# FCStellarisSCH.net
KiCad netlist of a schematic drawn in Altium Designer
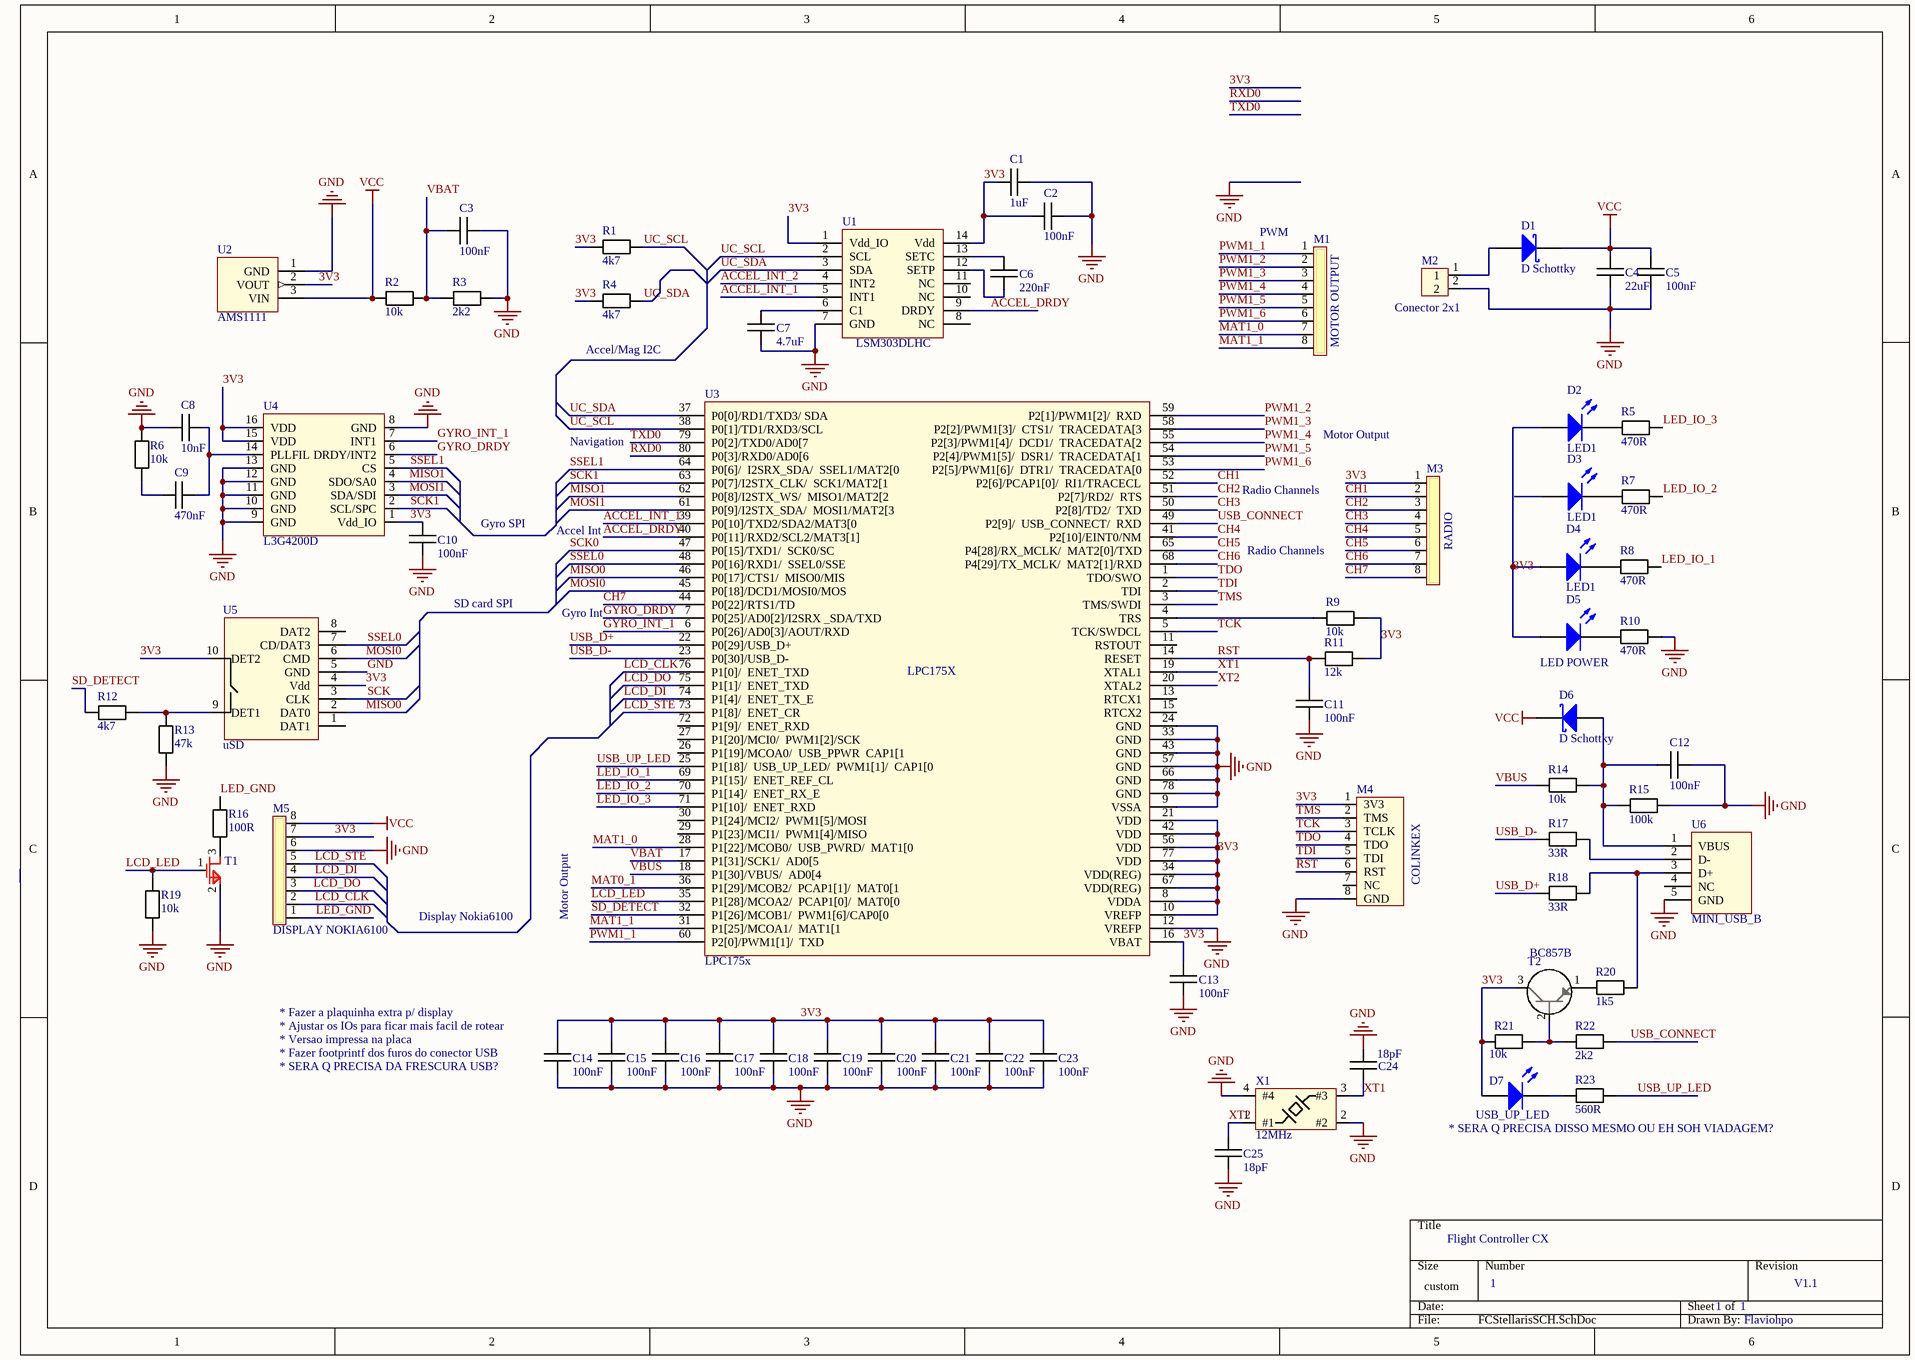
[diagram p0: FCStellarisSCH.SchDoc]

(export (version "E")
  (design (tool "Eeschema 10.0.6"))
  (components
    (comp (ref "C1")
      (value "1uF")
      (footprint "Capacitor 0805")
      (description "Capacitor")
      (libsource (lib "altiumflaviolibSH") (part "Capacitor"))
    )
    (comp (ref "C2")
      (value "100nF")
      (footprint "Capacitor 0805")
      (description "Capacitor")
      (libsource (lib "altiumflaviolibSH") (part "Capacitor"))
    )
    (comp (ref "C3")
      (value "100nF")
      (footprint "Capacitor 0805")
      (description "Capacitor")
      (libsource (lib "altiumflaviolibSH") (part "Capacitor"))
    )
    (comp (ref "C4")
      (value "22uF")
      (footprint "Capacitor 0805")
      (description "Capacitor")
      (libsource (lib "altiumflaviolibSH") (part "Capacitor"))
    )
    (comp (ref "C5")
      (value "100nF")
      (footprint "Capacitor 0805")
      (description "Capacitor")
      (libsource (lib "altiumflaviolibSH") (part "Capacitor"))
    )
    (comp (ref "C6")
      (value "220nF")
      (footprint "Capacitor 0805")
      (description "Capacitor")
      (libsource (lib "altiumflaviolibSH") (part "Capacitor"))
    )
    (comp (ref "C7")
      (value "4.7uF")
      (footprint "Capacitor 0805")
      (description "Capacitor")
      (libsource (lib "altiumflaviolibSH") (part "Capacitor"))
    )
    (comp (ref "C8")
      (value "10nF")
      (footprint "Capacitor 0805")
      (description "Capacitor")
      (libsource (lib "altiumflaviolibSH") (part "Capacitor"))
    )
    (comp (ref "C9")
      (value "470nF")
      (footprint "Capacitor 0805")
      (description "Capacitor")
      (libsource (lib "altiumflaviolibSH") (part "Capacitor"))
    )
    (comp (ref "C10")
      (value "100nF")
      (footprint "Capacitor 0805")
      (description "Capacitor")
      (libsource (lib "altiumflaviolibSH") (part "Capacitor"))
    )
    (comp (ref "C11")
      (value "100nF")
      (footprint "Capacitor 0805")
      (description "Capacitor")
      (libsource (lib "altiumflaviolibSH") (part "Capacitor"))
    )
    (comp (ref "C12")
      (value "100nF")
      (footprint "Capacitor 0805")
      (description "Capacitor")
      (libsource (lib "altiumflaviolibSH") (part "Capacitor"))
    )
    (comp (ref "C13")
      (value "100nF")
      (footprint "Capacitor 0805")
      (description "Capacitor")
      (libsource (lib "altiumflaviolibSH") (part "Capacitor"))
    )
    (comp (ref "C14")
      (value "100nF")
      (footprint "Capacitor 0805")
      (description "Capacitor")
      (libsource (lib "altiumflaviolibSH") (part "Capacitor"))
    )
    (comp (ref "C15")
      (value "100nF")
      (footprint "Capacitor 0805")
      (description "Capacitor")
      (libsource (lib "altiumflaviolibSH") (part "Capacitor"))
    )
    (comp (ref "C16")
      (value "100nF")
      (footprint "Capacitor 0805")
      (description "Capacitor")
      (libsource (lib "altiumflaviolibSH") (part "Capacitor"))
    )
    (comp (ref "C17")
      (value "100nF")
      (footprint "Capacitor 0805")
      (description "Capacitor")
      (libsource (lib "altiumflaviolibSH") (part "Capacitor"))
    )
    (comp (ref "C18")
      (value "100nF")
      (footprint "Capacitor 0805")
      (description "Capacitor")
      (libsource (lib "altiumflaviolibSH") (part "Capacitor"))
    )
    (comp (ref "C19")
      (value "100nF")
      (footprint "Capacitor 0805")
      (description "Capacitor")
      (libsource (lib "altiumflaviolibSH") (part "Capacitor"))
    )
    (comp (ref "C20")
      (value "100nF")
      (footprint "Capacitor 0805")
      (description "Capacitor")
      (libsource (lib "altiumflaviolibSH") (part "Capacitor"))
    )
    (comp (ref "C21")
      (value "100nF")
      (footprint "Capacitor 0805")
      (description "Capacitor")
      (libsource (lib "altiumflaviolibSH") (part "Capacitor"))
    )
    (comp (ref "C22")
      (value "100nF")
      (footprint "Capacitor 0805")
      (description "Capacitor")
      (libsource (lib "altiumflaviolibSH") (part "Capacitor"))
    )
    (comp (ref "C23")
      (value "100nF")
      (footprint "Capacitor 0805")
      (description "Capacitor")
      (libsource (lib "altiumflaviolibSH") (part "Capacitor"))
    )
    (comp (ref "C24")
      (value "18pF")
      (footprint "Capacitor 0805")
      (description "Capacitor")
      (libsource (lib "altiumflaviolibSH") (part "Capacitor"))
    )
    (comp (ref "C25")
      (value "18pF")
      (footprint "Capacitor 0805")
      (description "Capacitor")
      (libsource (lib "altiumflaviolibSH") (part "Capacitor"))
    )
    (comp (ref "D1")
      (value "D Schottky")
      (footprint "SMB")
      (description "Schottky Diode")
      (fields (field (name "PUBLISHER") "Altium Limited"))
      (libsource (lib "Miscellaneous Devices") (part "D Schottky"))
    )
    (comp (ref "D2")
      (value "LED1")
      (footprint "led0805")
      (description "Typical RED GaAs LED")
      (fields (field (name "PUBLISHER") "Altium Limited"))
      (libsource (lib "Miscellaneous Devices") (part "LED1"))
    )
    (comp (ref "D3")
      (value "LED1")
      (footprint "led0805")
      (description "Typical RED GaAs LED")
      (fields (field (name "PUBLISHER") "Altium Limited"))
      (libsource (lib "Miscellaneous Devices") (part "LED1"))
    )
    (comp (ref "D4")
      (value "LED1")
      (footprint "led0805")
      (description "Typical RED, GREEN, YELLOW, AMBER GaAs LED")
      (fields (field (name "PUBLISHER") "Altium Limited"))
      (libsource (lib "Miscellaneous Devices") (part "LED2"))
    )
    (comp (ref "D5")
      (value "LED POWER")
      (footprint "3.2X1.6X1.1")
      (description "Typical RED, GREEN, YELLOW, AMBER GaAs LED")
      (fields (field (name "PUBLISHER") "Altium Limited"))
      (libsource (lib "Miscellaneous Devices") (part "LED2"))
    )
    (comp (ref "D6")
      (value "D Schottky")
      (footprint "SMB")
      (description "Schottky Diode")
      (fields (field (name "PUBLISHER") "Altium Limited"))
      (libsource (lib "Miscellaneous Devices") (part "D Schottky"))
    )
    (comp (ref "D7")
      (value "USB_UP_LED")
      (footprint "led0805")
      (description "Typical RED GaAs LED")
      (fields (field (name "PUBLISHER") "Altium Limited"))
      (libsource (lib "Miscellaneous Devices") (part "LED1"))
    )
    (comp (ref "M1")
      (value "MOTOR OUTPUT")
      (footprint "Molex8 1.25 pitch Housing SMD")
      (libsource (lib "altiumflaviolibSH") (part "conector127-8x1"))
    )
    (comp (ref "M2")
      (value "Conector 2x1")
      (footprint "altiumflaviolib:Con256M2x1")
      (libsource (lib "altiumflaviolibSH") (part "conector254-2x1"))
    )
    (comp (ref "M3")
      (value "RADIO")
      (footprint "Molex8 1.25 pitch Housing SMD")
      (libsource (lib "altiumflaviolibSH") (part "conector127-8x1"))
    )
    (comp (ref "M4")
      (value "COLINKEX")
      (footprint "PinHead8 2.54mm")
      (libsource (lib "altiumflaviolibSH") (part "JTAG_COLINKEX"))
    )
    (comp (ref "M5")
      (value "DISPLAY NOKIA6100")
      (footprint "Molex8 1.25 pitch Housing SMD")
      (libsource (lib "") (part "conector127-8x1_1"))
    )
    (comp (ref "R1")
      (value "4k7")
      (footprint "Resistor 0805")
      (description "Resisitor")
      (libsource (lib "altiumflaviolibSH") (part "Resisitor"))
    )
    (comp (ref "R2")
      (value "10k")
      (footprint "Resistor 0805")
      (description "Resisitor")
      (libsource (lib "altiumflaviolibSH") (part "Resisitor"))
    )
    (comp (ref "R3")
      (value "2k2")
      (footprint "Resistor 0805")
      (description "Resisitor")
      (libsource (lib "altiumflaviolibSH") (part "Resisitor"))
    )
    (comp (ref "R4")
      (value "4k7")
      (footprint "Resistor 0805")
      (description "Resisitor")
      (libsource (lib "altiumflaviolibSH") (part "Resisitor"))
    )
    (comp (ref "R5")
      (value "470R")
      (footprint "Resistor 0805")
      (description "Resisitor")
      (libsource (lib "altiumflaviolibSH") (part "Resisitor"))
    )
    (comp (ref "R6")
      (value "10k")
      (footprint "Resistor 0805")
      (description "Resisitor")
      (libsource (lib "altiumflaviolibSH") (part "Resisitor"))
    )
    (comp (ref "R7")
      (value "470R")
      (footprint "Resistor 0805")
      (description "Resisitor")
      (libsource (lib "altiumflaviolibSH") (part "Resisitor"))
    )
    (comp (ref "R8")
      (value "470R")
      (footprint "Resistor 0805")
      (description "Resisitor")
      (libsource (lib "altiumflaviolibSH") (part "Resisitor"))
    )
    (comp (ref "R9")
      (value "10k")
      (footprint "Resistor 0805")
      (description "Resisitor")
      (libsource (lib "altiumflaviolibSH") (part "Resisitor"))
    )
    (comp (ref "R10")
      (value "470R")
      (footprint "Resistor 0805")
      (description "Resisitor")
      (libsource (lib "altiumflaviolibSH") (part "Resisitor"))
    )
    (comp (ref "R11")
      (value "12k")
      (footprint "Resistor 0805")
      (description "Resisitor")
      (libsource (lib "altiumflaviolibSH") (part "Resisitor"))
    )
    (comp (ref "R12")
      (value "4k7")
      (footprint "Resistor 0805")
      (description "Resisitor")
      (libsource (lib "altiumflaviolibSH") (part "Resisitor"))
    )
    (comp (ref "R13")
      (value "47k")
      (footprint "Resistor 0805")
      (description "Resisitor")
      (libsource (lib "altiumflaviolibSH") (part "Resisitor"))
    )
    (comp (ref "R14")
      (value "10k")
      (footprint "Resistor 0805")
      (description "Resisitor")
      (libsource (lib "altiumflaviolibSH") (part "Resisitor"))
    )
    (comp (ref "R15")
      (value "100k")
      (footprint "Resistor 0805")
      (description "Resisitor")
      (libsource (lib "altiumflaviolibSH") (part "Resisitor"))
    )
    (comp (ref "R16")
      (value "100R")
      (footprint "Resistor 0805")
      (description "Resisitor")
      (libsource (lib "altiumflaviolibSH") (part "Resisitor"))
    )
    (comp (ref "R17")
      (value "33R")
      (footprint "Resistor 0805")
      (description "Resisitor")
      (libsource (lib "altiumflaviolibSH") (part "Resisitor"))
    )
    (comp (ref "R18")
      (value "33R")
      (footprint "Resistor 0805")
      (description "Resisitor")
      (libsource (lib "altiumflaviolibSH") (part "Resisitor"))
    )
    (comp (ref "R19")
      (value "10k")
      (footprint "Resistor 0805")
      (description "Resisitor")
      (libsource (lib "altiumflaviolibSH") (part "Resisitor"))
    )
    (comp (ref "R20")
      (value "1k5")
      (footprint "Resistor 0805")
      (description "Resisitor")
      (libsource (lib "altiumflaviolibSH") (part "Resisitor"))
    )
    (comp (ref "R21")
      (value "10k")
      (footprint "Resistor 0805")
      (description "Resisitor")
      (libsource (lib "altiumflaviolibSH") (part "Resisitor"))
    )
    (comp (ref "R22")
      (value "2k2")
      (footprint "Resistor 0805")
      (description "Resisitor")
      (libsource (lib "altiumflaviolibSH") (part "Resisitor"))
    )
    (comp (ref "R23")
      (value "560R")
      (footprint "Resistor 0805")
      (description "Resisitor")
      (libsource (lib "altiumflaviolibSH") (part "Resisitor"))
    )
    (comp (ref "T1")
      (value "MOSFET_NPN")
      (footprint "SOT23 - 123")
      (libsource (lib "altiumflaviolibSH") (part "MOSFET_NPN"))
    )
    (comp (ref "T2")
      (value "BC857B")
      (footprint "SOT23 - 213")
      (libsource (lib "altiumflaviolibSH") (part "BC857B"))
    )
    (comp (ref "U1")
      (value "LSM303DLHC")
      (footprint "LGA-14")
      (description "3-axis Compass and accelerometer I2C Interface")
      (libsource (lib "altiumflaviolibSH") (part "LSM303DLHC"))
    )
    (comp (ref "U2")
      (value "AMS1111")
      (footprint "AMS1111")
      (description "3.3V Linear Regulator")
      (libsource (lib "altiumflaviolibSH") (part "AMS1111"))
    )
    (comp (ref "U3")
      (value "LPC175x")
      (footprint "SQFP50P1400X1400-80L")
      (libsource (lib "altiumflaviolibSH") (part "LPC175x"))
    )
    (comp (ref "U4")
      (value "L3G4200D")
      (footprint "altiumflaviolib:LGA16")
      (description "Digital Gyroscope 3-axis")
      (libsource (lib "altiumflaviolibSH") (part "L3G4200D"))
    )
    (comp (ref "U5")
      (value "uSD")
      (footprint "MICRO SDCARD")
      (libsource (lib "altiumflaviolibSH") (part "MICROSD"))
    )
    (comp (ref "U6")
      (value "MINI_USB_B")
      (footprint "altiumflaviolib:USB_MINI_B")
      (libsource (lib "altiumflaviolibSH") (part "MINI_USB_B"))
    )
    (comp (ref "X1")
      (value "12MHz")
      (footprint "XTAL-3.2x2.5")
      (libsource (lib "altiumflaviolibSH") (part "XTAL4PIN"))
    )
  )
  (nets
    (net (code "1") (name "/3V3") (class "Default")
      (node (ref "C1") (pin "2") (pinfunction "2_2") (pintype "passive"))
      (node (ref "C10") (pin "1") (pinfunction "1_1") (pintype "passive"))
      (node (ref "C13") (pin "2") (pinfunction "2_2") (pintype "passive"))
      (node (ref "C14") (pin "2") (pinfunction "2_2") (pintype "passive"))
      (node (ref "C15") (pin "2") (pinfunction "2_2") (pintype "passive"))
      (node (ref "C16") (pin "2") (pinfunction "2_2") (pintype "passive"))
      (node (ref "C17") (pin "2") (pinfunction "2_2") (pintype "passive"))
      (node (ref "C18") (pin "2") (pinfunction "2_2") (pintype "passive"))
      (node (ref "C19") (pin "2") (pinfunction "2_2") (pintype "passive"))
      (node (ref "C2") (pin "1") (pinfunction "1_1") (pintype "passive"))
      (node (ref "C20") (pin "2") (pinfunction "2_2") (pintype "passive"))
      (node (ref "C21") (pin "2") (pinfunction "2_2") (pintype "passive"))
      (node (ref "C22") (pin "2") (pinfunction "2_2") (pintype "passive"))
      (node (ref "C23") (pin "2") (pinfunction "2_2") (pintype "passive"))
      (node (ref "D2") (pin "1") (pinfunction "A_1") (pintype "passive"))
      (node (ref "D4") (pin "1") (pinfunction "A_1") (pintype "passive"))
      (node (ref "D5") (pin "1") (pinfunction "A_1") (pintype "passive"))
      (node (ref "D7") (pin "1") (pinfunction "A_1") (pintype "passive"))
      (node (ref "M3") (pin "1") (pintype "passive"))
      (node (ref "M4") (pin "1") (pinfunction "3V3_1") (pintype "passive"))
      (node (ref "M5") (pin "7") (pintype "passive"))
      (node (ref "R1") (pin "1") (pinfunction "1_1") (pintype "passive"))
      (node (ref "R11") (pin "1") (pinfunction "1_1") (pintype "passive"))
      (node (ref "R21") (pin "2") (pinfunction "2_2") (pintype "passive"))
      (node (ref "R4") (pin "1") (pinfunction "1_1") (pintype "passive"))
      (node (ref "R9") (pin "1") (pinfunction "1_1") (pintype "passive"))
      (node (ref "T2") (pin "3") (pinfunction "C_3") (pintype "passive"))
      (node (ref "U1") (pin "1") (pinfunction "Vdd_IO_1") (pintype "passive"))
      (node (ref "U1") (pin "14") (pinfunction "Vdd_14") (pintype "passive"))
      (node (ref "U2") (pin "2") (pinfunction "VOUT_2") (pintype "output"))
      (node (ref "U3") (pin "10") (pinfunction "VREFP_10") (pintype "passive"))
      (node (ref "U3") (pin "16") (pinfunction "VBAT_16") (pintype "passive"))
      (node (ref "U3") (pin "21") (pinfunction "VDD_21") (pintype "passive"))
      (node (ref "U3") (pin "34") (pinfunction "VDD(REG)_34") (pintype "passive"))
      (node (ref "U3") (pin "42") (pinfunction "VDD_42") (pintype "passive"))
      (node (ref "U3") (pin "56") (pinfunction "VDD_56") (pintype "passive"))
      (node (ref "U3") (pin "67") (pinfunction "VDD(REG)_67") (pintype "passive"))
      (node (ref "U3") (pin "77") (pinfunction "VDD_77") (pintype "passive"))
      (node (ref "U3") (pin "8") (pinfunction "VDDA_8") (pintype "passive"))
      (node (ref "U4") (pin "1") (pinfunction "Vdd_IO_1") (pintype "passive"))
      (node (ref "U4") (pin "15") (pinfunction "VDD_15") (pintype "passive"))
      (node (ref "U4") (pin "16") (pinfunction "VDD_16") (pintype "passive"))
      (node (ref "U5") (pin "10") (pinfunction "DET2_10") (pintype "passive"))
      (node (ref "U5") (pin "4") (pinfunction "Vdd_4") (pintype "passive"))
    )
    (net (code "3") (name "/ACCEL_DRDY") (class "Default")
      (node (ref "U1") (pin "9") (pinfunction "DRDY_9") (pintype "passive"))
      (node (ref "U3") (pin "40") (pinfunction "P0[11]/RXD2/SCL2/MAT3[1]_40") (pintype "passive"))
    )
    (net (code "4") (name "/ACCEL_INT_1") (class "Default")
      (node (ref "U1") (pin "5") (pinfunction "INT1_5") (pintype "passive"))
      (node (ref "U3") (pin "39") (pinfunction "P0[10]/TXD2/SDA2/MAT3[0_39") (pintype "passive"))
    )
    (net (code "5") (name "/ACCEL_INT_2") (class "Default")
      (node (ref "U1") (pin "4") (pinfunction "INT2_4") (pintype "passive"))
    )
    (net (code "6") (name "/CH1") (class "Default")
      (node (ref "M3") (pin "2") (pintype "passive"))
      (node (ref "U3") (pin "52") (pinfunction "P2[6]/PCAP1[0]/__RI1/TRACECL_52") (pintype "passive"))
    )
    (net (code "7") (name "/CH2") (class "Default")
      (node (ref "M3") (pin "3") (pintype "passive"))
      (node (ref "U3") (pin "51") (pinfunction "P2[7]/RD2/__RTS_51") (pintype "passive"))
    )
    (net (code "8") (name "/CH3") (class "Default")
      (node (ref "M3") (pin "4") (pintype "passive"))
      (node (ref "U3") (pin "50") (pinfunction "P2[8]/TD2/__TXD_50") (pintype "passive"))
    )
    (net (code "9") (name "/CH4") (class "Default")
      (node (ref "M3") (pin "5") (pintype "passive"))
      (node (ref "U3") (pin "41") (pinfunction "P2[10]/EINT0/NM_41") (pintype "passive"))
    )
    (net (code "10") (name "/CH5") (class "Default")
      (node (ref "M3") (pin "6") (pintype "passive"))
      (node (ref "U3") (pin "65") (pinfunction "P4[28]/RX_MCLK/__MAT2[0]/TXD_65") (pintype "passive"))
    )
    (net (code "11") (name "/CH6") (class "Default")
      (node (ref "M3") (pin "7") (pintype "passive"))
      (node (ref "U3") (pin "68") (pinfunction "P4[29]/TX_MCLK/__MAT2[1]/RXD_68") (pintype "passive"))
    )
    (net (code "12") (name "/CH7") (class "Default")
      (node (ref "M3") (pin "8") (pintype "passive"))
      (node (ref "U3") (pin "44") (pinfunction "P0[22]/RTS1/TD_44") (pintype "passive"))
    )
    (net (code "13") (name "/GYRO_DRDY") (class "Default")
      (node (ref "U3") (pin "7") (pinfunction "P0[25]/AD0[2]/I2SRX__SDA/TXD_7") (pintype "passive"))
      (node (ref "U4") (pin "6") (pinfunction "DRDY/INT2_6") (pintype "passive"))
    )
    (net (code "14") (name "/GYRO_INT_1") (class "Default")
      (node (ref "U3") (pin "6") (pinfunction "P0[26]/AD0[3]/AOUT/RXD_6") (pintype "passive"))
      (node (ref "U4") (pin "7") (pinfunction "INT1_7") (pintype "passive"))
    )
    (net (code "15") (name "/LCD_CLK") (class "Default")
      (node (ref "M5") (pin "2") (pintype "passive"))
      (node (ref "U3") (pin "76") (pinfunction "P1[0]/__ENET_TXD_76") (pintype "passive"))
    )
    (net (code "16") (name "/LCD_DI") (class "Default")
      (node (ref "M5") (pin "4") (pintype "passive"))
      (node (ref "U3") (pin "74") (pinfunction "P1[4]/__ENET_TX_E_74") (pintype "passive"))
    )
    (net (code "17") (name "/LCD_DO") (class "Default")
      (node (ref "M5") (pin "3") (pintype "passive"))
      (node (ref "U3") (pin "75") (pinfunction "P1[1]/__ENET_TXD_75") (pintype "passive"))
    )
    (net (code "18") (name "/LCD_LED") (class "Default")
      (node (ref "R19") (pin "2") (pinfunction "2_2") (pintype "passive"))
      (node (ref "T1") (pin "1") (pinfunction "G_1") (pintype "passive"))
      (node (ref "U3") (pin "35") (pinfunction "P1[28]/MCOA2/__PCAP1[0]/__MAT0[0_35") (pintype "passive"))
    )
    (net (code "19") (name "/LCD_STE") (class "Default")
      (node (ref "M5") (pin "5") (pintype "passive"))
      (node (ref "U3") (pin "73") (pinfunction "P1[8]/__ENET_CR_73") (pintype "passive"))
    )
    (net (code "20") (name "/LED_GND") (class "Default")
      (node (ref "M5") (pin "1") (pintype "passive"))
      (node (ref "R16") (pin "2") (pinfunction "2_2") (pintype "passive"))
    )
    (net (code "21") (name "/LED_IO_1") (class "Default")
      (node (ref "R8") (pin "2") (pinfunction "2_2") (pintype "passive"))
      (node (ref "U3") (pin "69") (pinfunction "P1[15]/__ENET_REF_CL_69") (pintype "passive"))
    )
    (net (code "22") (name "/LED_IO_2") (class "Default")
      (node (ref "R7") (pin "2") (pinfunction "2_2") (pintype "passive"))
      (node (ref "U3") (pin "70") (pinfunction "P1[14]/__ENET_RX_E_70") (pintype "passive"))
    )
    (net (code "23") (name "/LED_IO_3") (class "Default")
      (node (ref "R5") (pin "2") (pinfunction "2_2") (pintype "passive"))
      (node (ref "U3") (pin "71") (pinfunction "P1[10]/__ENET_RXD_71") (pintype "passive"))
    )
    (net (code "24") (name "/MAT0_1") (class "Default")
      (node (ref "U3") (pin "36") (pinfunction "P1[29]/MCOB2/__PCAP1[1]/__MAT0[1_36") (pintype "passive"))
    )
    (net (code "25") (name "/MAT1_0") (class "Default")
      (node (ref "M1") (pin "7") (pintype "passive"))
      (node (ref "U3") (pin "28") (pinfunction "P1[22]/MCOB0/__USB_PWRD/__MAT1[0_28") (pintype "passive"))
    )
    (net (code "26") (name "/MAT1_1") (class "Default")
      (node (ref "M1") (pin "8") (pintype "passive"))
      (node (ref "U3") (pin "31") (pinfunction "P1[25]/MCOA1/__MAT1[1_31") (pintype "passive"))
    )
    (net (code "27") (name "/MISO0") (class "Default")
      (node (ref "U3") (pin "46") (pinfunction "P0[17]/CTS1/__MISO0/MIS_46") (pintype "passive"))
      (node (ref "U5") (pin "2") (pinfunction "DAT0_2") (pintype "passive"))
    )
    (net (code "28") (name "/MISO1") (class "Default")
      (node (ref "U3") (pin "62") (pinfunction "P0[8]/I2STX_WS/__MISO1/MAT2[2_62") (pintype "passive"))
      (node (ref "U4") (pin "4") (pinfunction "SDO/SA0_4") (pintype "passive"))
    )
    (net (code "29") (name "/MOSI0") (class "Default")
      (node (ref "U3") (pin "45") (pinfunction "P0[18]/DCD1/MOSI0/MOS_45") (pintype "passive"))
      (node (ref "U5") (pin "6") (pinfunction "CMD_6") (pintype "passive"))
    )
    (net (code "30") (name "/MOSI1") (class "Default")
      (node (ref "U3") (pin "61") (pinfunction "P0[9]/I2STX_SDA/__MOSI1/MAT2[3_61") (pintype "passive"))
      (node (ref "U4") (pin "3") (pinfunction "SDA/SDI_3") (pintype "passive"))
    )
    (net (code "31") (name "/PWM1_1") (class "Default")
      (node (ref "M1") (pin "1") (pintype "passive"))
      (node (ref "U3") (pin "60") (pinfunction "P2[0]/PWM1[1]/__TXD_60") (pintype "passive"))
    )
    (net (code "32") (name "/PWM1_2") (class "Default")
      (node (ref "M1") (pin "2") (pintype "passive"))
      (node (ref "U3") (pin "59") (pinfunction "P2[1]/PWM1[2]/__RXD_59") (pintype "passive"))
    )
    (net (code "33") (name "/PWM1_3") (class "Default")
      (node (ref "M1") (pin "3") (pintype "passive"))
      (node (ref "U3") (pin "58") (pinfunction "P2[2]/PWM1[3]/__CTS1/__TRACEDATA[3_58") (pintype "passive"))
    )
    (net (code "34") (name "/PWM1_4") (class "Default")
      (node (ref "M1") (pin "4") (pintype "passive"))
      (node (ref "U3") (pin "55") (pinfunction "P2[3]/PWM1[4]/__DCD1/__TRACEDATA[2_55") (pintype "passive"))
    )
    (net (code "35") (name "/PWM1_5") (class "Default")
      (node (ref "M1") (pin "5") (pintype "passive"))
      (node (ref "U3") (pin "54") (pinfunction "P2[4]/PWM1[5]/__DSR1/__TRACEDATA[1_54") (pintype "passive"))
    )
    (net (code "36") (name "/PWM1_6") (class "Default")
      (node (ref "M1") (pin "6") (pintype "passive"))
      (node (ref "U3") (pin "53") (pinfunction "P2[5]/PWM1[6]/__DTR1/__TRACEDATA[0_53") (pintype "passive"))
    )
    (net (code "37") (name "/RST") (class "Default")
      (node (ref "C11") (pin "2") (pinfunction "2_2") (pintype "passive"))
      (node (ref "M4") (pin "6") (pinfunction "RST_6") (pintype "passive"))
      (node (ref "R11") (pin "2") (pinfunction "2_2") (pintype "passive"))
      (node (ref "U3") (pin "14") (pinfunction "RESET_14") (pintype "passive"))
    )
    (net (code "38") (name "/RXD0") (class "Default")
      (node (ref "U3") (pin "80") (pinfunction "P0[3]/RXD0/AD0[6_80") (pintype "passive"))
    )
    (net (code "39") (name "/SCK") (class "Default")
      (node (ref "U5") (pin "3") (pinfunction "CLK_3") (pintype "passive"))
    )
    (net (code "40") (name "/SCK0") (class "Default")
      (node (ref "U3") (pin "47") (pinfunction "P0[15]/TXD1/__SCK0/SC_47") (pintype "passive"))
    )
    (net (code "41") (name "/SCK1") (class "Default")
      (node (ref "U3") (pin "63") (pinfunction "P0[7]/I2STX_CLK/__SCK1/MAT2[1_63") (pintype "passive"))
      (node (ref "U4") (pin "2") (pinfunction "SCL/SPC_2") (pintype "passive"))
    )
    (net (code "42") (name "/SD_DETECT") (class "Default")
      (node (ref "R12") (pin "1") (pinfunction "1_1") (pintype "passive"))
      (node (ref "U3") (pin "32") (pinfunction "P1[26]/MCOB1/__PWM1[6]/CAP0[0_32") (pintype "passive"))
    )
    (net (code "43") (name "/SSEL0") (class "Default")
      (node (ref "U3") (pin "48") (pinfunction "P0[16]/RXD1/__SSEL0/SSE_48") (pintype "passive"))
      (node (ref "U5") (pin "7") (pinfunction "CD/DAT3_7") (pintype "passive"))
    )
    (net (code "44") (name "/SSEL1") (class "Default")
      (node (ref "U3") (pin "64") (pinfunction "P0[6]/__I2SRX_SDA/__SSEL1/MAT2[0_64") (pintype "passive"))
      (node (ref "U4") (pin "5") (pinfunction "CS_5") (pintype "passive"))
    )
    (net (code "45") (name "/TCK") (class "Default")
      (node (ref "M4") (pin "3") (pinfunction "TCLK_3") (pintype "passive"))
      (node (ref "U3") (pin "5") (pinfunction "TCK/SWDCL_5") (pintype "passive"))
    )
    (net (code "46") (name "/TDI") (class "Default")
      (node (ref "M4") (pin "5") (pinfunction "TDI_5") (pintype "passive"))
      (node (ref "U3") (pin "2") (pinfunction "TDI_2") (pintype "passive"))
    )
    (net (code "47") (name "/TDO") (class "Default")
      (node (ref "M4") (pin "4") (pinfunction "TDO_4") (pintype "passive"))
      (node (ref "U3") (pin "1") (pinfunction "TDO/SWO_1") (pintype "passive"))
    )
    (net (code "48") (name "/TMS") (class "Default")
      (node (ref "M4") (pin "2") (pinfunction "TMS_2") (pintype "passive"))
      (node (ref "U3") (pin "3") (pinfunction "TMS/SWDI_3") (pintype "passive"))
    )
    (net (code "49") (name "/TXD0") (class "Default")
      (node (ref "U3") (pin "79") (pinfunction "P0[2]/TXD0/AD0[7_79") (pintype "passive"))
    )
    (net (code "50") (name "/UC_SCL") (class "Default")
      (node (ref "R1") (pin "2") (pinfunction "2_2") (pintype "passive"))
      (node (ref "U1") (pin "2") (pinfunction "SCL_2") (pintype "passive"))
      (node (ref "U3") (pin "38") (pinfunction "P0[1]/TD1/RXD3/SCL_38") (pintype "passive"))
    )
    (net (code "51") (name "/UC_SDA") (class "Default")
      (node (ref "R4") (pin "2") (pinfunction "2_2") (pintype "passive"))
      (node (ref "U1") (pin "3") (pinfunction "SDA_3") (pintype "passive"))
      (node (ref "U3") (pin "37") (pinfunction "P0[0]/RD1/TXD3/_SDA_37") (pintype "passive"))
    )
    (net (code "52") (name "/USB_CONNECT") (class "Default")
      (node (ref "R22") (pin "1") (pinfunction "1_1") (pintype "passive"))
      (node (ref "U3") (pin "49") (pinfunction "P2[9]/__USB_CONNECT/__RXD_49") (pintype "passive"))
    )
    (net (code "53") (name "/USB_D+") (class "Default")
      (node (ref "R18") (pin "1") (pinfunction "1_1") (pintype "passive"))
      (node (ref "U3") (pin "22") (pinfunction "P0[29]/USB_D+_22") (pintype "passive"))
    )
    (net (code "54") (name "/USB_D-") (class "Default")
      (node (ref "R17") (pin "1") (pinfunction "1_1") (pintype "passive"))
      (node (ref "U3") (pin "23") (pinfunction "P0[30]/USB_D-_23") (pintype "passive"))
    )
    (net (code "55") (name "/USB_UP_LED") (class "Default")
      (node (ref "R23") (pin "1") (pinfunction "1_1") (pintype "passive"))
      (node (ref "U3") (pin "25") (pinfunction "P1[18]/__USB_UP_LED/__PWM1[1]/__CAP1[0_25") (pintype "passive"))
    )
    (net (code "56") (name "/VBAT") (class "Default")
      (node (ref "C3") (pin "1") (pinfunction "1_1") (pintype "passive"))
      (node (ref "R2") (pin "2") (pinfunction "2_2") (pintype "passive"))
      (node (ref "R3") (pin "1") (pinfunction "1_1") (pintype "passive"))
      (node (ref "U3") (pin "17") (pinfunction "P1[31]/SCK1/__AD0[5_17") (pintype "passive"))
    )
    (net (code "57") (name "/VBUS") (class "Default")
      (node (ref "R14") (pin "1") (pinfunction "1_1") (pintype "passive"))
      (node (ref "U3") (pin "18") (pinfunction "P1[30]/VBUS/__AD0[4_18") (pintype "passive"))
    )
    (net (code "58") (name "/XT1") (class "Default")
      (node (ref "C24") (pin "1") (pinfunction "1_1") (pintype "passive"))
      (node (ref "U3") (pin "19") (pinfunction "XTAL1_19") (pintype "passive"))
      (node (ref "X1") (pin "3") (pinfunction "#3_3") (pintype "passive"))
    )
    (net (code "59") (name "/XT2") (class "Default")
      (node (ref "C25") (pin "2") (pinfunction "2_2") (pintype "passive"))
      (node (ref "U3") (pin "20") (pinfunction "XTAL2_20") (pintype "passive"))
      (node (ref "X1") (pin "1") (pinfunction "#1_1") (pintype "passive"))
    )
    (net (code "60") (name "GND") (class "Default")
      (node (ref "C1") (pin "1") (pinfunction "1_1") (pintype "passive"))
      (node (ref "C10") (pin "2") (pinfunction "2_2") (pintype "passive"))
      (node (ref "C11") (pin "1") (pinfunction "1_1") (pintype "passive"))
      (node (ref "C12") (pin "2") (pinfunction "2_2") (pintype "passive"))
      (node (ref "C13") (pin "1") (pinfunction "1_1") (pintype "passive"))
      (node (ref "C14") (pin "1") (pinfunction "1_1") (pintype "passive"))
      (node (ref "C15") (pin "1") (pinfunction "1_1") (pintype "passive"))
      (node (ref "C16") (pin "1") (pinfunction "1_1") (pintype "passive"))
      (node (ref "C17") (pin "1") (pinfunction "1_1") (pintype "passive"))
      (node (ref "C18") (pin "1") (pinfunction "1_1") (pintype "passive"))
      (node (ref "C19") (pin "1") (pinfunction "1_1") (pintype "passive"))
      (node (ref "C2") (pin "2") (pinfunction "2_2") (pintype "passive"))
      (node (ref "C20") (pin "1") (pinfunction "1_1") (pintype "passive"))
      (node (ref "C21") (pin "1") (pinfunction "1_1") (pintype "passive"))
      (node (ref "C22") (pin "1") (pinfunction "1_1") (pintype "passive"))
      (node (ref "C23") (pin "1") (pinfunction "1_1") (pintype "passive"))
      (node (ref "C24") (pin "2") (pinfunction "2_2") (pintype "passive"))
      (node (ref "C25") (pin "1") (pinfunction "1_1") (pintype "passive"))
      (node (ref "C3") (pin "2") (pinfunction "2_2") (pintype "passive"))
      (node (ref "C4") (pin "1") (pinfunction "1_1") (pintype "passive"))
      (node (ref "C5") (pin "1") (pinfunction "1_1") (pintype "passive"))
      (node (ref "C7") (pin "2") (pinfunction "2_2") (pintype "passive"))
      (node (ref "C8") (pin "2") (pinfunction "2_2") (pintype "passive"))
      (node (ref "M2") (pin "2") (pinfunction "2_2") (pintype "passive"))
      (node (ref "M4") (pin "8") (pinfunction "GND_8") (pintype "passive"))
      (node (ref "M5") (pin "6") (pintype "passive"))
      (node (ref "R10") (pin "2") (pinfunction "2_2") (pintype "passive"))
      (node (ref "R13") (pin "1") (pinfunction "1_1") (pintype "passive"))
      (node (ref "R15") (pin "2") (pinfunction "2_2") (pintype "passive"))
      (node (ref "R19") (pin "1") (pinfunction "1_1") (pintype "passive"))
      (node (ref "R3") (pin "2") (pinfunction "2_2") (pintype "passive"))
      (node (ref "R6") (pin "1") (pinfunction "1_1") (pintype "passive"))
      (node (ref "T1") (pin "2") (pinfunction "S_2") (pintype "passive"))
      (node (ref "U1") (pin "7") (pinfunction "GND_7") (pintype "passive"))
      (node (ref "U2") (pin "1") (pinfunction "GND_1") (pintype "power_in"))
      (node (ref "U3") (pin "12") (pinfunction "VREFP_12") (pintype "passive"))
      (node (ref "U3") (pin "24") (pinfunction "GND_24") (pintype "passive"))
      (node (ref "U3") (pin "33") (pinfunction "GND_33") (pintype "passive"))
      (node (ref "U3") (pin "43") (pinfunction "GND_43") (pintype "passive"))
      (node (ref "U3") (pin "57") (pinfunction "GND_57") (pintype "passive"))
      (node (ref "U3") (pin "66") (pinfunction "GND_66") (pintype "passive"))
      (node (ref "U3") (pin "78") (pinfunction "GND_78") (pintype "passive"))
      (node (ref "U3") (pin "9") (pinfunction "VSSA_9") (pintype "passive"))
      (node (ref "U4") (pin "10") (pinfunction "GND_10") (pintype "passive"))
      (node (ref "U4") (pin "11") (pinfunction "GND_11") (pintype "passive"))
      (node (ref "U4") (pin "12") (pinfunction "GND_12") (pintype "passive"))
      (node (ref "U4") (pin "13") (pinfunction "GND_13") (pintype "passive"))
      (node (ref "U4") (pin "8") (pinfunction "GND_8") (pintype "passive"))
      (node (ref "U4") (pin "9") (pinfunction "GND_9") (pintype "passive"))
      (node (ref "U5") (pin "5") (pinfunction "GND_5") (pintype "passive"))
      (node (ref "U6") (pin "5") (pinfunction "GND_5") (pintype "passive"))
      (node (ref "X1") (pin "2") (pinfunction "#2_2") (pintype "passive"))
      (node (ref "X1") (pin "4") (pinfunction "#4_4") (pintype "passive"))
    )
    (net (code "61") (name "Net-(C9-Pad2)") (class "Default")
      (node (ref "C9") (pin "2") (pinfunction "2_2") (pintype "passive"))
      (node (ref "R6") (pin "2") (pinfunction "2_2") (pintype "passive"))
    )
    (net (code "62") (name "Net-(D1-A)") (class "Default")
      (node (ref "D1") (pin "1") (pinfunction "A_1") (pintype "passive"))
      (node (ref "M2") (pin "1") (pinfunction "1_1") (pintype "passive"))
    )
    (net (code "63") (name "Net-(D2-K)") (class "Default")
      (node (ref "D2") (pin "2") (pinfunction "K_2") (pintype "passive"))
      (node (ref "R5") (pin "1") (pinfunction "1_1") (pintype "passive"))
    )
    (net (code "64") (name "Net-(D3-K)") (class "Default")
      (node (ref "D3") (pin "2") (pinfunction "K_2") (pintype "passive"))
      (node (ref "R7") (pin "1") (pinfunction "1_1") (pintype "passive"))
    )
    (net (code "65") (name "Net-(D4-K)") (class "Default")
      (node (ref "D4") (pin "2") (pinfunction "K_2") (pintype "passive"))
      (node (ref "R8") (pin "1") (pinfunction "1_1") (pintype "passive"))
    )
    (net (code "66") (name "Net-(D5-K)") (class "Default")
      (node (ref "D5") (pin "2") (pinfunction "K_2") (pintype "passive"))
      (node (ref "R10") (pin "1") (pinfunction "1_1") (pintype "passive"))
    )
    (net (code "67") (name "Net-(D6-A)") (class "Default")
      (node (ref "C12") (pin "1") (pinfunction "1_1") (pintype "passive"))
      (node (ref "D6") (pin "1") (pinfunction "A_1") (pintype "passive"))
      (node (ref "R14") (pin "2") (pinfunction "2_2") (pintype "passive"))
      (node (ref "R15") (pin "1") (pinfunction "1_1") (pintype "passive"))
      (node (ref "U6") (pin "1") (pinfunction "VBUS_1") (pintype "passive"))
    )
    (net (code "68") (name "Net-(D7-K)") (class "Default")
      (node (ref "D7") (pin "2") (pinfunction "K_2") (pintype "passive"))
      (node (ref "R23") (pin "2") (pinfunction "2_2") (pintype "passive"))
    )
    (net (code "69") (name "Net-(T1-D)") (class "Default")
      (node (ref "R16") (pin "1") (pinfunction "1_1") (pintype "passive"))
      (node (ref "T1") (pin "3") (pinfunction "D_3") (pintype "passive"))
    )
    (net (code "70") (name "Net-(T2-B)") (class "Default")
      (node (ref "R21") (pin "1") (pinfunction "1_1") (pintype "passive"))
      (node (ref "R22") (pin "2") (pinfunction "2_2") (pintype "passive"))
      (node (ref "T2") (pin "2") (pinfunction "B_2") (pintype "passive"))
    )
    (net (code "71") (name "Net-(T2-E)") (class "Default")
      (node (ref "R20") (pin "2") (pinfunction "2_2") (pintype "passive"))
      (node (ref "T2") (pin "1") (pinfunction "E_1") (pintype "passive"))
    )
    (net (code "72") (name "Net-(U1-C1)") (class "Default")
      (node (ref "C7") (pin "1") (pinfunction "1_1") (pintype "passive"))
      (node (ref "U1") (pin "6") (pinfunction "C1_6") (pintype "passive"))
    )
    (net (code "73") (name "Net-(U1-SETC)") (class "Default")
      (node (ref "C6") (pin "2") (pinfunction "2_2") (pintype "passive"))
      (node (ref "U1") (pin "13") (pinfunction "SETC_13") (pintype "passive"))
    )
    (net (code "74") (name "Net-(U1-SETP)") (class "Default")
      (node (ref "C6") (pin "1") (pinfunction "1_1") (pintype "passive"))
      (node (ref "U1") (pin "12") (pinfunction "SETP_12") (pintype "passive"))
    )
    (net (code "75") (name "Net-(U3-TRS)") (class "Default")
      (node (ref "R9") (pin "2") (pinfunction "2_2") (pintype "passive"))
      (node (ref "U3") (pin "4") (pinfunction "TRS_4") (pintype "passive"))
    )
    (net (code "76") (name "Net-(U4-PLLFIL)") (class "Default")
      (node (ref "C8") (pin "1") (pinfunction "1_1") (pintype "passive"))
      (node (ref "C9") (pin "1") (pinfunction "1_1") (pintype "passive"))
      (node (ref "U4") (pin "14") (pinfunction "PLLFIL_14") (pintype "passive"))
    )
    (net (code "77") (name "Net-(U5-DET1)") (class "Default")
      (node (ref "R12") (pin "2") (pinfunction "2_2") (pintype "passive"))
      (node (ref "R13") (pin "2") (pinfunction "2_2") (pintype "passive"))
      (node (ref "U5") (pin "9") (pinfunction "DET1_9") (pintype "passive"))
    )
    (net (code "78") (name "Net-(U6-D+)") (class "Default")
      (node (ref "R18") (pin "2") (pinfunction "2_2") (pintype "passive"))
      (node (ref "R20") (pin "1") (pinfunction "1_1") (pintype "passive"))
      (node (ref "U6") (pin "3") (pinfunction "D+_3") (pintype "passive"))
    )
    (net (code "79") (name "Net-(U6-D-)") (class "Default")
      (node (ref "R17") (pin "2") (pinfunction "2_2") (pintype "passive"))
      (node (ref "U6") (pin "2") (pinfunction "D-_2") (pintype "passive"))
    )
    (net (code "80") (name "VCC") (class "Default")
      (node (ref "C4") (pin "2") (pinfunction "2_2") (pintype "passive"))
      (node (ref "C5") (pin "2") (pinfunction "2_2") (pintype "passive"))
      (node (ref "D1") (pin "2") (pinfunction "K_2") (pintype "passive"))
      (node (ref "D6") (pin "2") (pinfunction "K_2") (pintype "passive"))
      (node (ref "M5") (pin "8") (pintype "passive"))
      (node (ref "R2") (pin "1") (pinfunction "1_1") (pintype "passive"))
      (node (ref "U2") (pin "3") (pinfunction "VIN_3") (pintype "power_in"))
    )
    (net (code "81") (name "unconnected-(D3-A-Pad1)") (class "Default")
      (node (ref "D3") (pin "1") (pinfunction "A_1") (pintype "passive"))
    )
    (net (code "82") (name "unconnected-(M4-NC-Pad7)") (class "Default")
      (node (ref "M4") (pin "7") (pinfunction "NC_7") (pintype "passive"))
    )
    (net (code "83") (name "unconnected-(U1-NC-Pad8)") (class "Default")
      (node (ref "U1") (pin "8") (pinfunction "NC_8") (pintype "passive"))
    )
    (net (code "84") (name "unconnected-(U1-NC-Pad10)") (class "Default")
      (node (ref "U1") (pin "10") (pinfunction "NC_10") (pintype "passive"))
    )
    (net (code "85") (name "unconnected-(U1-NC-Pad11)") (class "Default")
      (node (ref "U1") (pin "11") (pinfunction "NC_11") (pintype "passive"))
    )
    (net (code "86") (name "unconnected-(U3-P1[9]{slash}__ENET_RXD-Pad72)") (class "Default")
      (node (ref "U3") (pin "72") (pinfunction "P1[9]/__ENET_RXD_72") (pintype "passive"))
    )
    (net (code "87") (name "unconnected-(U3-P1[19]{slash}MCOA0{slash}__USB_PPWR__CAP1[1-Pad26)") (class "Default")
      (node (ref "U3") (pin "26") (pinfunction "P1[19]/MCOA0/__USB_PPWR__CAP1[1_26") (pintype "passive"))
    )
    (net (code "88") (name "unconnected-(U3-P1[20]{slash}MCI0{slash}__PWM1[2]{slash}SCK-Pad27)") (class "Default")
      (node (ref "U3") (pin "27") (pinfunction "P1[20]/MCI0/__PWM1[2]/SCK_27") (pintype "passive"))
    )
    (net (code "89") (name "unconnected-(U3-P1[23]{slash}MCI1{slash}__PWM1[4]{slash}MISO-Pad29)") (class "Default")
      (node (ref "U3") (pin "29") (pinfunction "P1[23]/MCI1/__PWM1[4]/MISO_29") (pintype "passive"))
    )
    (net (code "90") (name "unconnected-(U3-P1[24]{slash}MCI2{slash}__PWM1[5]{slash}MOSI-Pad30)") (class "Default")
      (node (ref "U3") (pin "30") (pinfunction "P1[24]/MCI2/__PWM1[5]/MOSI_30") (pintype "passive"))
    )
    (net (code "91") (name "unconnected-(U3-RSTOUT-Pad11)") (class "Default")
      (node (ref "U3") (pin "11") (pinfunction "RSTOUT_11") (pintype "passive"))
    )
    (net (code "92") (name "unconnected-(U3-RTCX1-Pad13)") (class "Default")
      (node (ref "U3") (pin "13") (pinfunction "RTCX1_13") (pintype "passive"))
    )
    (net (code "93") (name "unconnected-(U3-RTCX2-Pad15)") (class "Default")
      (node (ref "U3") (pin "15") (pinfunction "RTCX2_15") (pintype "passive"))
    )
    (net (code "94") (name "unconnected-(U5-DAT1-Pad1)") (class "Default")
      (node (ref "U5") (pin "1") (pinfunction "DAT1_1") (pintype "passive"))
    )
    (net (code "95") (name "unconnected-(U5-DAT2-Pad8)") (class "Default")
      (node (ref "U5") (pin "8") (pinfunction "DAT2_8") (pintype "passive"))
    )
    (net (code "96") (name "unconnected-(U6-NC-Pad4)") (class "Default")
      (node (ref "U6") (pin "4") (pinfunction "NC_4") (pintype "passive"))
    )
  )
)
